# Sheet.net
KiCad netlist of a schematic drawn in Altium Designer
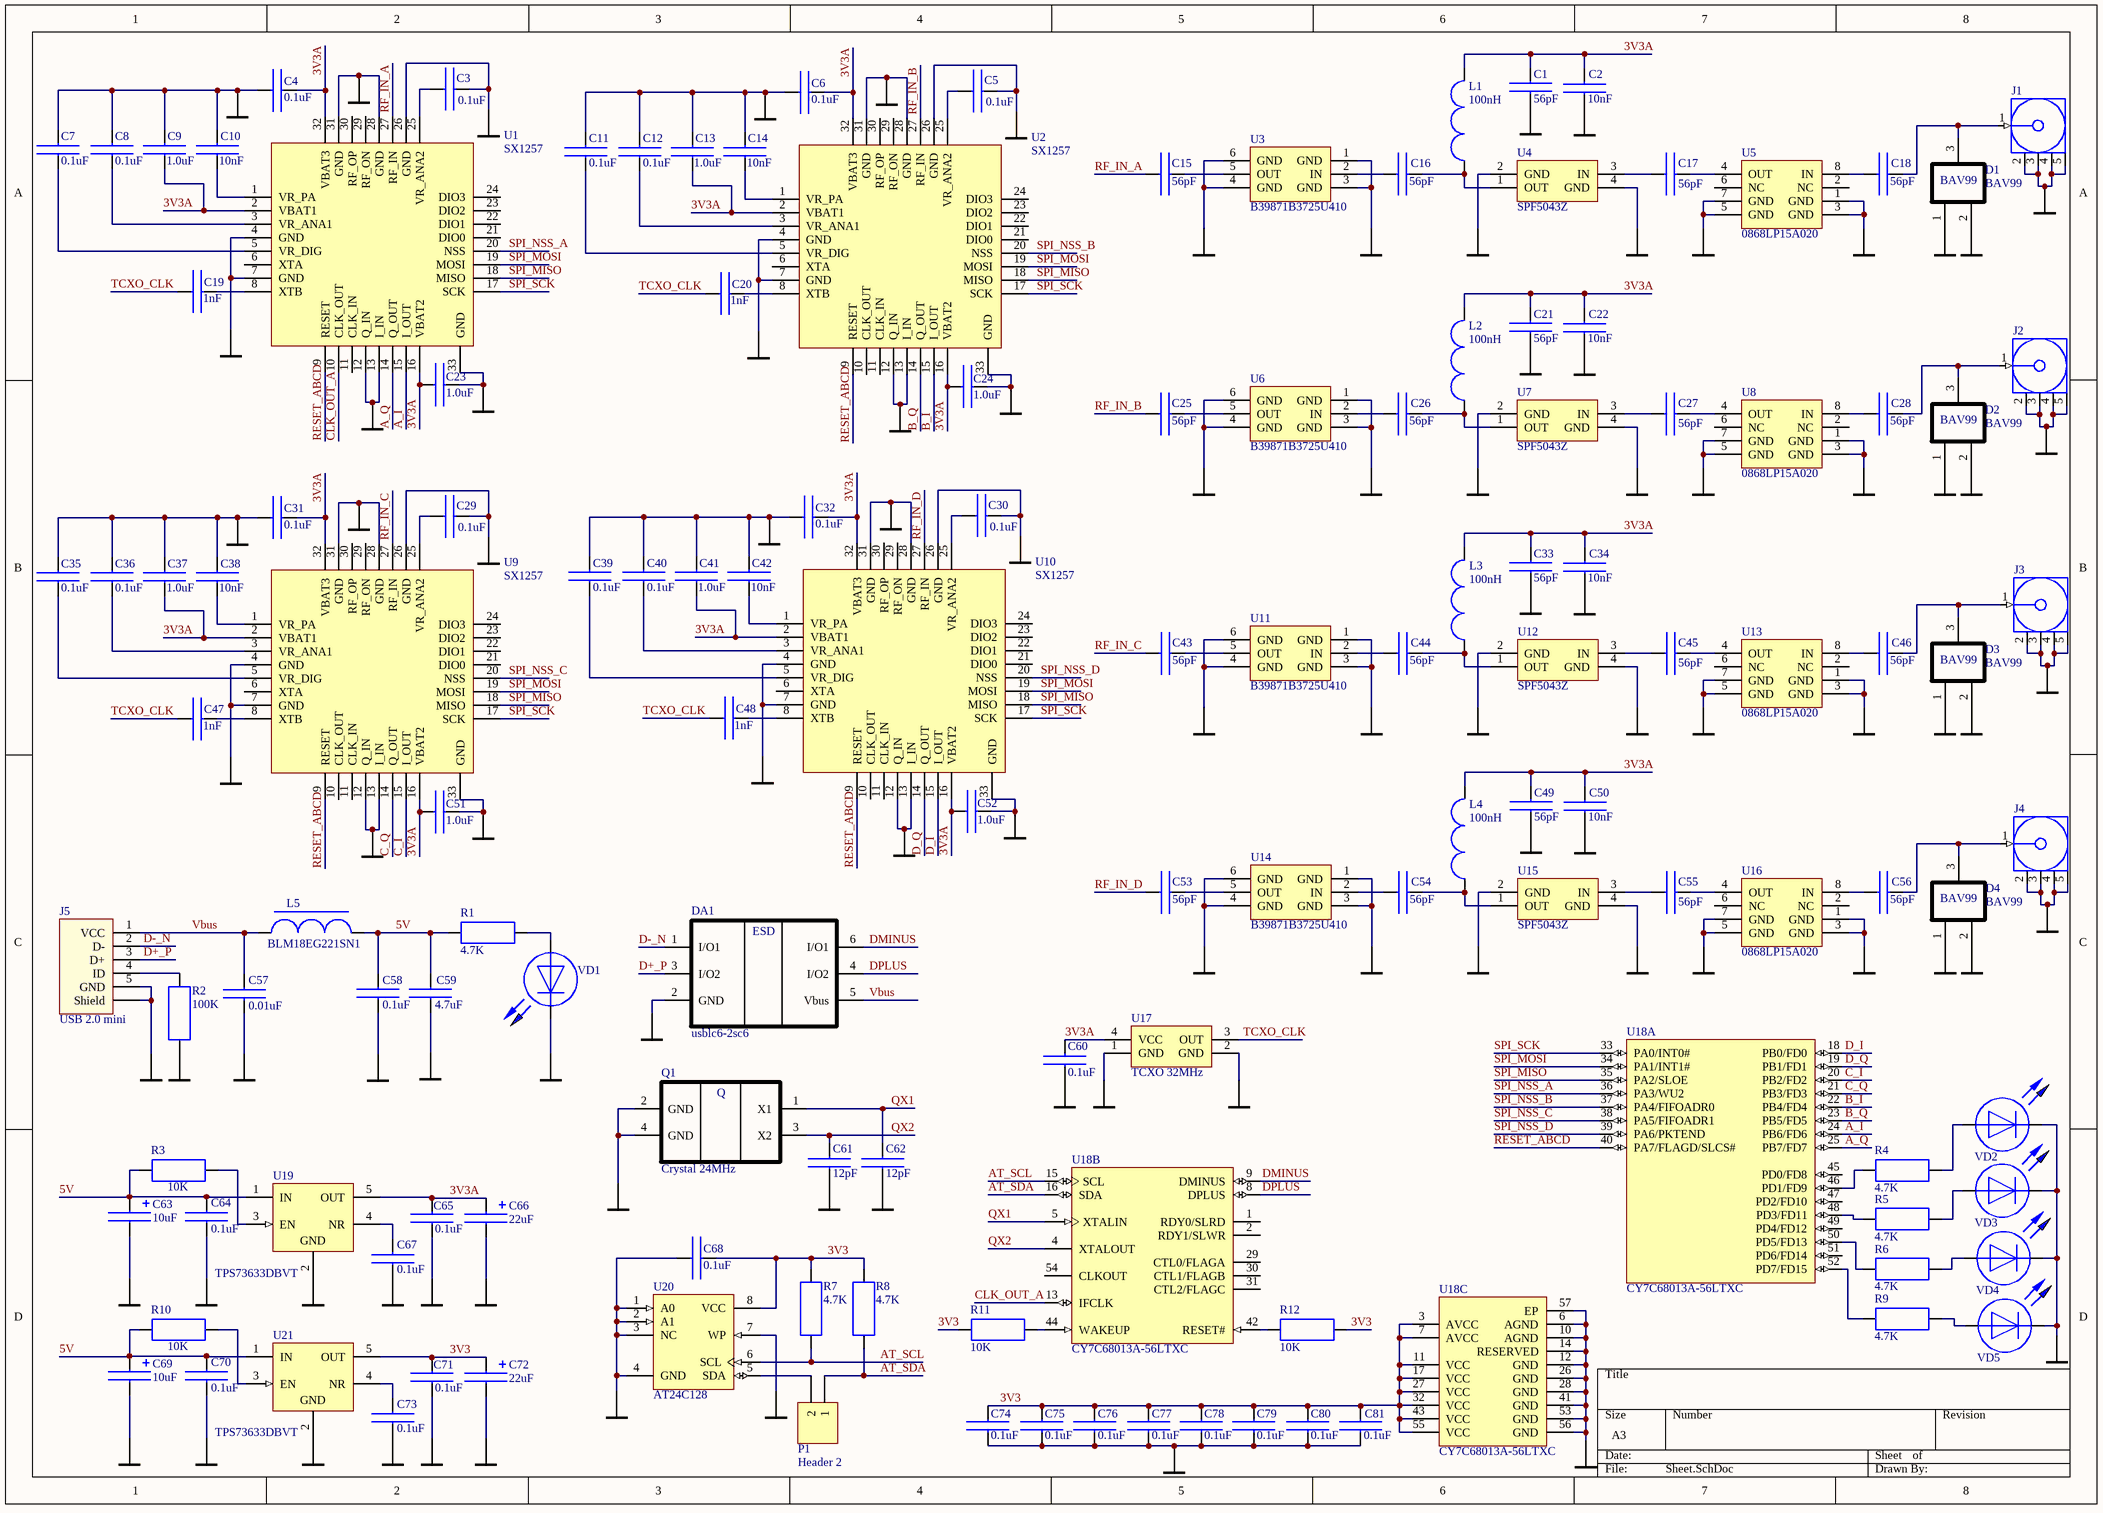
[diagram p0: Sheet.SchDoc]

(export (version "E")
  (design (tool "Eeschema 10.0.6"))
  (components
    (comp (ref "C1") (value "56pF") (footprint "CAP(0603)") (libsource (lib "Schlib1") (part "CAP")))
    (comp (ref "C2") (value "10nF") (footprint "CAP(0603)") (libsource (lib "Schlib1") (part "CAP")))
    (comp (ref "C3") (value "0.1uF") (footprint "CAP(0603)") (libsource (lib "Schlib1") (part "CAP")))
    (comp (ref "C4") (value "0.1uF") (footprint "CAP(0603)") (libsource (lib "Schlib1") (part "CAP")))
    (comp (ref "C5") (value "0.1uF") (footprint "CAP(0603)") (libsource (lib "Schlib1") (part "CAP")))
    (comp (ref "C6") (value "0.1uF") (footprint "CAP(0603)") (libsource (lib "Schlib1") (part "CAP")))
    (comp (ref "C7") (value "0.1uF") (footprint "CAP(0603)") (libsource (lib "Schlib1") (part "CAP")))
    (comp (ref "C8") (value "0.1uF") (footprint "CAP(0603)") (libsource (lib "Schlib1") (part "CAP")))
    (comp (ref "C9") (value "1.0uF") (footprint "CAP(0603)") (libsource (lib "Schlib1") (part "CAP")))
    (comp (ref "C10") (value "10nF") (footprint "CAP(0603)") (libsource (lib "Schlib1") (part "CAP")))
    (comp (ref "C11") (value "0.1uF") (footprint "CAP(0603)") (libsource (lib "Schlib1") (part "CAP")))
    (comp (ref "C12") (value "0.1uF") (footprint "CAP(0603)") (libsource (lib "Schlib1") (part "CAP")))
    (comp (ref "C13") (value "1.0uF") (footprint "CAP(0603)") (libsource (lib "Schlib1") (part "CAP")))
    (comp (ref "C14") (value "10nF") (footprint "CAP(0603)") (libsource (lib "Schlib1") (part "CAP")))
    (comp (ref "C15") (value "56pF") (footprint "CAP(0603)") (libsource (lib "Schlib1") (part "CAP")))
    (comp (ref "C16") (value "56pF") (footprint "CAP(0603)") (libsource (lib "Schlib1") (part "CAP")))
    (comp (ref "C17") (value "56pF") (footprint "CAP(0603)") (libsource (lib "Schlib1") (part "CAP")))
    (comp (ref "C18") (value "56pF") (footprint "CAP(0603)") (libsource (lib "Schlib1") (part "CAP")))
    (comp (ref "C19") (value "1nF") (footprint "CAP(0603)") (libsource (lib "Schlib1") (part "CAP")))
    (comp (ref "C20") (value "1nF") (footprint "CAP(0603)") (libsource (lib "Schlib1") (part "CAP")))
    (comp (ref "C21") (value "56pF") (footprint "CAP(0603)") (libsource (lib "Schlib1") (part "CAP")))
    (comp (ref "C22") (value "10nF") (footprint "CAP(0603)") (libsource (lib "Schlib1") (part "CAP")))
    (comp (ref "C23") (value "1.0uF") (footprint "CAP(0603)") (libsource (lib "Schlib1") (part "CAP")))
    (comp (ref "C24") (value "1.0uF") (footprint "CAP(0603)") (libsource (lib "Schlib1") (part "CAP")))
    (comp (ref "C25") (value "56pF") (footprint "CAP(0603)") (libsource (lib "Schlib1") (part "CAP")))
    (comp (ref "C26") (value "56pF") (footprint "CAP(0603)") (libsource (lib "Schlib1") (part "CAP")))
    (comp (ref "C27") (value "56pF") (footprint "CAP(0603)") (libsource (lib "Schlib1") (part "CAP")))
    (comp (ref "C28") (value "56pF") (footprint "CAP(0603)") (libsource (lib "Schlib1") (part "CAP")))
    (comp (ref "C29") (value "0.1uF") (footprint "CAP(0603)") (libsource (lib "Schlib1") (part "CAP")))
    (comp (ref "C30") (value "0.1uF") (footprint "CAP(0603)") (libsource (lib "Schlib1") (part "CAP")))
    (comp (ref "C31") (value "0.1uF") (footprint "CAP(0603)") (libsource (lib "Schlib1") (part "CAP")))
    (comp (ref "C32") (value "0.1uF") (footprint "CAP(0603)") (libsource (lib "Schlib1") (part "CAP")))
    (comp (ref "C33") (value "56pF") (footprint "CAP(0603)") (libsource (lib "Schlib1") (part "CAP")))
    (comp (ref "C34") (value "10nF") (footprint "CAP(0603)") (libsource (lib "Schlib1") (part "CAP")))
    (comp (ref "C35") (value "0.1uF") (footprint "CAP(0603)") (libsource (lib "Schlib1") (part "CAP")))
    (comp (ref "C36") (value "0.1uF") (footprint "CAP(0603)") (libsource (lib "Schlib1") (part "CAP")))
    (comp (ref "C37") (value "1.0uF") (footprint "CAP(0603)") (libsource (lib "Schlib1") (part "CAP")))
    (comp (ref "C38") (value "10nF") (footprint "CAP(0603)") (libsource (lib "Schlib1") (part "CAP")))
    (comp (ref "C39") (value "0.1uF") (footprint "CAP(0603)") (libsource (lib "Schlib1") (part "CAP")))
    (comp (ref "C40") (value "0.1uF") (footprint "CAP(0603)") (libsource (lib "Schlib1") (part "CAP")))
    (comp (ref "C41") (value "1.0uF") (footprint "CAP(0603)") (libsource (lib "Schlib1") (part "CAP")))
    (comp (ref "C42") (value "10nF") (footprint "CAP(0603)") (libsource (lib "Schlib1") (part "CAP")))
    (comp (ref "C43") (value "56pF") (footprint "CAP(0603)") (libsource (lib "Schlib1") (part "CAP")))
    (comp (ref "C44") (value "56pF") (footprint "CAP(0603)") (libsource (lib "Schlib1") (part "CAP")))
    (comp (ref "C45") (value "56pF") (footprint "CAP(0603)") (libsource (lib "Schlib1") (part "CAP")))
    (comp (ref "C46") (value "56pF") (footprint "CAP(0603)") (libsource (lib "Schlib1") (part "CAP")))
    (comp (ref "C47") (value "1nF") (footprint "CAP(0603)") (libsource (lib "Schlib1") (part "CAP")))
    (comp (ref "C48") (value "1nF") (footprint "CAP(0603)") (libsource (lib "Schlib1") (part "CAP")))
    (comp (ref "C49") (value "56pF") (footprint "CAP(0603)") (libsource (lib "Schlib1") (part "CAP")))
    (comp (ref "C50") (value "10nF") (footprint "CAP(0603)") (libsource (lib "Schlib1") (part "CAP")))
    (comp (ref "C51") (value "1.0uF") (footprint "CAP(0603)") (libsource (lib "Schlib1") (part "CAP")))
    (comp (ref "C52") (value "1.0uF") (footprint "CAP(0603)") (libsource (lib "Schlib1") (part "CAP")))
    (comp (ref "C53") (value "56pF") (footprint "CAP(0603)") (libsource (lib "Schlib1") (part "CAP")))
    (comp (ref "C54") (value "56pF") (footprint "CAP(0603)") (libsource (lib "Schlib1") (part "CAP")))
    (comp (ref "C55") (value "56pF") (footprint "CAP(0603)") (libsource (lib "Schlib1") (part "CAP")))
    (comp (ref "C56") (value "56pF") (footprint "CAP(0603)") (libsource (lib "Schlib1") (part "CAP")))
    (comp (ref "C57") (value "0.01uF") (footprint "CAP(0603)") (libsource (lib "Schlib1") (part "CAP")))
    (comp (ref "C58") (value "0.1uF") (footprint "CAP(0603)") (libsource (lib "Schlib1") (part "CAP")))
    (comp (ref "C59") (value "4.7uF") (footprint "CAP(0603)") (libsource (lib "Schlib1") (part "CAP")))
    (comp (ref "C60") (value "0.1uF") (footprint "CAP(0603)") (libsource (lib "Schlib1") (part "CAP")))
    (comp (ref "C61") (value "12pF") (footprint "CAP(0603)") (libsource (lib "Schlib1") (part "CAP")))
    (comp (ref "C62") (value "12pF") (footprint "CAP(0603)") (libsource (lib "Schlib1") (part "CAP")))
    (comp (ref "C63")
      (value "10uF")
      (footprint "CC3216(1206)x18")
      (description "Tantalum SMD capacitor")
      (libsource (lib "Schlib1") (part "Tantalum"))
    )
    (comp (ref "C64") (value "0.1uF") (footprint "CAP(0603)") (libsource (lib "Schlib1") (part "CAP")))
    (comp (ref "C65") (value "0.1uF") (footprint "CAP(0603)") (libsource (lib "Schlib1") (part "CAP")))
    (comp (ref "C66")
      (value "22uF")
      (footprint "CC3216(1206)x18")
      (description "Tantalum SMD capacitor")
      (libsource (lib "Schlib1") (part "Tantalum"))
    )
    (comp (ref "C67") (value "0.1uF") (footprint "CAP(0603)") (libsource (lib "Schlib1") (part "CAP")))
    (comp (ref "C68") (value "0.1uF") (footprint "CAP(0603)") (libsource (lib "Schlib1") (part "CAP")))
    (comp (ref "C69")
      (value "10uF")
      (footprint "CC3216(1206)x18")
      (description "Tantalum SMD capacitor")
      (libsource (lib "Schlib1") (part "Tantalum"))
    )
    (comp (ref "C70") (value "0.1uF") (footprint "CAP(0603)") (libsource (lib "Schlib1") (part "CAP")))
    (comp (ref "C71") (value "0.1uF") (footprint "CAP(0603)") (libsource (lib "Schlib1") (part "CAP")))
    (comp (ref "C72")
      (value "22uF")
      (footprint "CC3216(1206)x18")
      (description "Tantalum SMD capacitor")
      (libsource (lib "Schlib1") (part "Tantalum"))
    )
    (comp (ref "C73") (value "0.1uF") (footprint "CAP(0603)") (libsource (lib "Schlib1") (part "CAP")))
    (comp (ref "C74") (value "0.1uF") (footprint "CAP(0603)") (libsource (lib "Schlib1") (part "CAP")))
    (comp (ref "C75") (value "0.1uF") (footprint "CAP(0603)") (libsource (lib "Schlib1") (part "CAP")))
    (comp (ref "C76") (value "0.1uF") (footprint "CAP(0603)") (libsource (lib "Schlib1") (part "CAP")))
    (comp (ref "C77") (value "0.1uF") (footprint "CAP(0603)") (libsource (lib "Schlib1") (part "CAP")))
    (comp (ref "C78") (value "0.1uF") (footprint "CAP(0603)") (libsource (lib "Schlib1") (part "CAP")))
    (comp (ref "C79") (value "0.1uF") (footprint "CAP(0603)") (libsource (lib "Schlib1") (part "CAP")))
    (comp (ref "C80") (value "0.1uF") (footprint "CAP(0603)") (libsource (lib "Schlib1") (part "CAP")))
    (comp (ref "C81") (value "0.1uF") (footprint "CAP(0603)") (libsource (lib "Schlib1") (part "CAP")))
    (comp (ref "D1") (value "BAV99") (footprint "SOT-23B") (libsource (lib "Schlib1") (part "BAV99")))
    (comp (ref "D2") (value "BAV99") (footprint "SOT-23B") (libsource (lib "Schlib1") (part "BAV99")))
    (comp (ref "D3") (value "BAV99") (footprint "SOT-23B") (libsource (lib "Schlib1") (part "BAV99")))
    (comp (ref "D4") (value "BAV99") (footprint "SOT-23B") (libsource (lib "Schlib1") (part "BAV99")))
    (comp (ref "DA1")
      (value "usblc6-2sc6")
      (footprint "SOT23-6L")
      (libsource (lib "Schlib1") (part "usblc6-2sc6"))
    )
    (comp (ref "J1")
      (value "60312202114514")
      (footprint "60312202114514")
      (description "WR-SMA SMA PCB End Launch Jack Flat Tab for 1.6 mm PCB")
      (fields (field (name "PUBLISHER") "Wurth Elektronik"))
      (libsource (lib "Schlib1") (part "60312202114514"))
    )
    (comp (ref "J2")
      (value "60312202114514")
      (footprint "60312202114514")
      (description "WR-SMA SMA PCB End Launch Jack Flat Tab for 1.6 mm PCB")
      (fields (field (name "PUBLISHER") "Wurth Elektronik"))
      (libsource (lib "Schlib1") (part "60312202114514"))
    )
    (comp (ref "J3")
      (value "60312202114514")
      (footprint "60312202114514")
      (description "WR-SMA SMA PCB End Launch Jack Flat Tab for 1.6 mm PCB")
      (fields (field (name "PUBLISHER") "Wurth Elektronik"))
      (libsource (lib "Schlib1") (part "60312202114514"))
    )
    (comp (ref "J4")
      (value "60312202114514")
      (footprint "60312202114514")
      (description "WR-SMA SMA PCB End Launch Jack Flat Tab for 1.6 mm PCB")
      (fields (field (name "PUBLISHER") "Wurth Elektronik"))
      (libsource (lib "Schlib1") (part "60312202114514"))
    )
    (comp (ref "J5")
      (value "USB 2.0 mini")
      (footprint "65100516121")
      (description "Mini USB 2.0 Type B SMT Horizontal 5 Contacts WR-COM")
      (libsource (lib "Schlib1") (part "USB 2.0 mini"))
    )
    (comp (ref "L1") (value "100nH") (footprint "L_0603") (libsource (lib "Schlib1") (part "IND")))
    (comp (ref "L2") (value "100nH") (footprint "L_0603") (libsource (lib "Schlib1") (part "IND")))
    (comp (ref "L3") (value "100nH") (footprint "L_0603") (libsource (lib "Schlib1") (part "IND")))
    (comp (ref "L4") (value "100nH") (footprint "L_0603") (libsource (lib "Schlib1") (part "IND")))
    (comp (ref "L5")
      (value "BLM18EG221SN1")
      (footprint "BLM18EG221SN1")
      (description "SMD Ferrite Bead 2A 220 Ohm(100MHz)")
      (libsource (lib "Schlib1") (part "BLM18EG221SN1"))
    )
    (comp (ref "P1")
      (value "Header 2")
      (footprint "HDR1X2")
      (description "Header, 2-Pin")
      (fields (field (name "PUBLISHER") "Altium Limited"))
      (libsource (lib "Miscellaneous Connectors") (part "Header 2"))
    )
    (comp (ref "Q1")
      (value "Crystal 24MHz")
      (footprint "SMD3225")
      (libsource (lib "Schlib1") (part "Crystal 24MHz"))
    )
    (comp (ref "R1")
      (value "4.7K")
      (footprint "RES(0603)")
      (description "Chip Resistor")
      (libsource (lib "Schlib1") (part "RES"))
    )
    (comp (ref "R2")
      (value "100K")
      (footprint "RES(0603)")
      (description "Chip Resistor")
      (libsource (lib "Schlib1") (part "RES"))
    )
    (comp (ref "R3")
      (value "10K")
      (footprint "RES(0603)")
      (description "Chip Resistor")
      (libsource (lib "Schlib1") (part "RES"))
    )
    (comp (ref "R4")
      (value "4.7K")
      (footprint "RES(0603)")
      (description "Chip Resistor")
      (libsource (lib "Schlib1") (part "RES"))
    )
    (comp (ref "R5")
      (value "4.7K")
      (footprint "RES(0603)")
      (description "Chip Resistor")
      (libsource (lib "Schlib1") (part "RES"))
    )
    (comp (ref "R6")
      (value "4.7K")
      (footprint "RES(0603)")
      (description "Chip Resistor")
      (libsource (lib "Schlib1") (part "RES"))
    )
    (comp (ref "R7")
      (value "4.7K")
      (footprint "RES(0603)")
      (description "Chip Resistor")
      (libsource (lib "Schlib1") (part "RES"))
    )
    (comp (ref "R8")
      (value "4.7K")
      (footprint "RES(0603)")
      (description "Chip Resistor")
      (libsource (lib "Schlib1") (part "RES"))
    )
    (comp (ref "R9")
      (value "4.7K")
      (footprint "RES(0603)")
      (description "Chip Resistor")
      (libsource (lib "Schlib1") (part "RES"))
    )
    (comp (ref "R10")
      (value "10K")
      (footprint "RES(0603)")
      (description "Chip Resistor")
      (libsource (lib "Schlib1") (part "RES"))
    )
    (comp (ref "R11")
      (value "10K")
      (footprint "RES(0603)")
      (description "Chip Resistor")
      (libsource (lib "Schlib1") (part "RES"))
    )
    (comp (ref "R12")
      (value "10K")
      (footprint "RES(0603)")
      (description "Chip Resistor")
      (libsource (lib "Schlib1") (part "RES"))
    )
    (comp (ref "U1") (value "SX1257") (footprint "QFN-32") (libsource (lib "Schlib1") (part "SX1257")))
    (comp (ref "U2") (value "SX1257") (footprint "QFN-32") (libsource (lib "Schlib1") (part "SX1257")))
    (comp (ref "U3")
      (value "B39871B3725U410")
      (footprint "SAW_Filter")
      (description "SAW Filter, 869MHz Center")
      (libsource (lib "Schlib1") (part "B39871B3725U410"))
    )
    (comp (ref "U4") (value "SPF5043Z") (footprint "SOT343-4") (libsource (lib "Schlib1") (part "SPF5043Z")))
    (comp (ref "U5")
      (value "0868LP15A020")
      (footprint "LPF868")
      (libsource (lib "Schlib1") (part "0868LP15A020"))
    )
    (comp (ref "U6")
      (value "B39871B3725U410")
      (footprint "SAW_Filter")
      (description "SAW Filter, 869MHz Center")
      (libsource (lib "Schlib1") (part "B39871B3725U410"))
    )
    (comp (ref "U7") (value "SPF5043Z") (footprint "SOT343-4") (libsource (lib "Schlib1") (part "SPF5043Z")))
    (comp (ref "U8")
      (value "0868LP15A020")
      (footprint "LPF868")
      (libsource (lib "Schlib1") (part "0868LP15A020"))
    )
    (comp (ref "U9") (value "SX1257") (footprint "QFN-32") (libsource (lib "Schlib1") (part "SX1257")))
    (comp (ref "U10") (value "SX1257") (footprint "QFN-32") (libsource (lib "Schlib1") (part "SX1257")))
    (comp (ref "U11")
      (value "B39871B3725U410")
      (footprint "SAW_Filter")
      (description "SAW Filter, 869MHz Center")
      (libsource (lib "Schlib1") (part "B39871B3725U410"))
    )
    (comp (ref "U12") (value "SPF5043Z") (footprint "SOT343-4") (libsource (lib "Schlib1") (part "SPF5043Z")))
    (comp (ref "U13")
      (value "0868LP15A020")
      (footprint "LPF868")
      (libsource (lib "Schlib1") (part "0868LP15A020"))
    )
    (comp (ref "U14")
      (value "B39871B3725U410")
      (footprint "SAW_Filter")
      (description "SAW Filter, 869MHz Center")
      (libsource (lib "Schlib1") (part "B39871B3725U410"))
    )
    (comp (ref "U15") (value "SPF5043Z") (footprint "SOT343-4") (libsource (lib "Schlib1") (part "SPF5043Z")))
    (comp (ref "U16")
      (value "0868LP15A020")
      (footprint "LPF868")
      (libsource (lib "Schlib1") (part "0868LP15A020"))
    )
    (comp (ref "U17") (value "TCXO 32MHz") (footprint "TCXO") (libsource (lib "Schlib1") (part "TCXO")))
    (comp (ref "U18")
      (value "CY7C68013A-56LTXC")
      (footprint "CYP-LTX56-5200X4500TP_N")
      (libsource (lib "Schlib1") (part "CY7C68013A-56LTXC"))
    )
    (comp (ref "U19")
      (value "TPS73633DBVT")
      (footprint "TI-DBV5_N")
      (fields (field (name "MANUFACTURER") "Texas Instruments"))
      (libsource (lib "Schlib1") (part "TPS73633DBVT"))
    )
    (comp (ref "U20") (value "AT24C128") (footprint "8S1_N") (libsource (lib "Schlib1") (part "AT24C128")))
    (comp (ref "U21")
      (value "TPS73633DBVT")
      (footprint "TI-DBV5_N")
      (fields (field (name "MANUFACTURER") "Texas Instruments"))
      (libsource (lib "Schlib1") (part "TPS73633DBVT"))
    )
    (comp (ref "VD1") (value "VD_6") (footprint "LED_0603") (libsource (lib "Schlib1") (part "VD_6")))
    (comp (ref "VD2") (value "VD_6") (footprint "LED_0603") (libsource (lib "Schlib1") (part "VD_6")))
    (comp (ref "VD3") (value "VD_6") (footprint "LED_0603") (libsource (lib "Schlib1") (part "VD_6")))
    (comp (ref "VD4") (value "VD_6") (footprint "LED_0603") (libsource (lib "Schlib1") (part "VD_6")))
    (comp (ref "VD5") (value "VD_6") (footprint "LED_0603") (libsource (lib "Schlib1") (part "VD_6")))
  )
  (nets
    (net (code "1") (name "/3V3") (class "Default")
      (node (ref "C68") (pin "2") (pintype "passive"))
      (node (ref "C71") (pin "2") (pintype "passive"))
      (node (ref "C72") (pin "1") (pintype "passive"))
      (node (ref "C74") (pin "2") (pintype "passive"))
      (node (ref "C75") (pin "2") (pintype "passive"))
      (node (ref "C76") (pin "2") (pintype "passive"))
      (node (ref "C77") (pin "2") (pintype "passive"))
      (node (ref "C78") (pin "2") (pintype "passive"))
      (node (ref "C79") (pin "2") (pintype "passive"))
      (node (ref "C80") (pin "2") (pintype "passive"))
      (node (ref "C81") (pin "2") (pintype "passive"))
      (node (ref "R11") (pin "1") (pintype "passive"))
      (node (ref "R12") (pin "2") (pintype "passive"))
      (node (ref "R7") (pin "2") (pintype "passive"))
      (node (ref "R8") (pin "2") (pintype "passive"))
      (node (ref "U18") (pin "11") (pinfunction "VCC_11") (pintype "power_in"))
      (node (ref "U18") (pin "17") (pinfunction "VCC_17") (pintype "power_in"))
      (node (ref "U18") (pin "27") (pinfunction "VCC_27") (pintype "power_in"))
      (node (ref "U18") (pin "3") (pinfunction "AVCC_3") (pintype "power_in"))
      (node (ref "U18") (pin "32") (pinfunction "VCC_32") (pintype "power_in"))
      (node (ref "U18") (pin "43") (pinfunction "VCC_43") (pintype "power_in"))
      (node (ref "U18") (pin "55") (pinfunction "VCC_55") (pintype "power_in"))
      (node (ref "U18") (pin "7") (pinfunction "AVCC_7") (pintype "power_in"))
      (node (ref "U20") (pin "8") (pinfunction "VCC_8") (pintype "power_in"))
      (node (ref "U21") (pin "5") (pinfunction "OUT_5") (pintype "power_in"))
    )
    (net (code "2") (name "/3V3A") (class "Default")
      (node (ref "C1") (pin "2") (pintype "passive"))
      (node (ref "C13") (pin "1") (pintype "passive"))
      (node (ref "C2") (pin "2") (pintype "passive"))
      (node (ref "C21") (pin "2") (pintype "passive"))
      (node (ref "C22") (pin "2") (pintype "passive"))
      (node (ref "C23") (pin "2") (pintype "passive"))
      (node (ref "C24") (pin "2") (pintype "passive"))
      (node (ref "C31") (pin "2") (pintype "passive"))
      (node (ref "C32") (pin "2") (pintype "passive"))
      (node (ref "C33") (pin "2") (pintype "passive"))
      (node (ref "C34") (pin "2") (pintype "passive"))
      (node (ref "C37") (pin "1") (pintype "passive"))
      (node (ref "C4") (pin "2") (pintype "passive"))
      (node (ref "C41") (pin "1") (pintype "passive"))
      (node (ref "C49") (pin "2") (pintype "passive"))
      (node (ref "C50") (pin "2") (pintype "passive"))
      (node (ref "C51") (pin "2") (pintype "passive"))
      (node (ref "C52") (pin "2") (pintype "passive"))
      (node (ref "C6") (pin "2") (pintype "passive"))
      (node (ref "C60") (pin "2") (pintype "passive"))
      (node (ref "C65") (pin "2") (pintype "passive"))
      (node (ref "C66") (pin "1") (pintype "passive"))
      (node (ref "C9") (pin "1") (pintype "passive"))
      (node (ref "L1") (pin "2") (pintype "passive"))
      (node (ref "L2") (pin "2") (pintype "passive"))
      (node (ref "L3") (pin "2") (pintype "passive"))
      (node (ref "L4") (pin "2") (pintype "passive"))
      (node (ref "U1") (pin "16") (pinfunction "VBAT2_16") (pintype "passive"))
      (node (ref "U1") (pin "2") (pinfunction "VBAT1_2") (pintype "passive"))
      (node (ref "U1") (pin "32") (pinfunction "VBAT3_32") (pintype "passive"))
      (node (ref "U10") (pin "16") (pinfunction "VBAT2_16") (pintype "passive"))
      (node (ref "U10") (pin "2") (pinfunction "VBAT1_2") (pintype "passive"))
      (node (ref "U10") (pin "32") (pinfunction "VBAT3_32") (pintype "passive"))
      (node (ref "U17") (pin "4") (pinfunction "VCC_4") (pintype "passive"))
      (node (ref "U19") (pin "5") (pinfunction "OUT_5") (pintype "power_in"))
      (node (ref "U2") (pin "16") (pinfunction "VBAT2_16") (pintype "passive"))
      (node (ref "U2") (pin "2") (pinfunction "VBAT1_2") (pintype "passive"))
      (node (ref "U2") (pin "32") (pinfunction "VBAT3_32") (pintype "passive"))
      (node (ref "U9") (pin "16") (pinfunction "VBAT2_16") (pintype "passive"))
      (node (ref "U9") (pin "2") (pinfunction "VBAT1_2") (pintype "passive"))
      (node (ref "U9") (pin "32") (pinfunction "VBAT3_32") (pintype "passive"))
    )
    (net (code "3") (name "/5V") (class "Default")
      (node (ref "C58") (pin "2") (pintype "passive"))
      (node (ref "C59") (pin "2") (pintype "passive"))
      (node (ref "C63") (pin "1") (pintype "passive"))
      (node (ref "C64") (pin "2") (pintype "passive"))
      (node (ref "C69") (pin "1") (pintype "passive"))
      (node (ref "C70") (pin "2") (pintype "passive"))
      (node (ref "L5") (pin "2") (pintype "passive"))
      (node (ref "R1") (pin "1") (pintype "passive"))
      (node (ref "R10") (pin "1") (pintype "passive"))
      (node (ref "R3") (pin "1") (pintype "passive"))
      (node (ref "U19") (pin "1") (pinfunction "IN_1") (pintype "power_in"))
      (node (ref "U21") (pin "1") (pinfunction "IN_1") (pintype "power_in"))
    )
    (net (code "4") (name "/AT_SCL") (class "Default")
      (node (ref "R7") (pin "1") (pintype "passive"))
      (node (ref "U18") (pin "15") (pinfunction "SCL_15") (pintype "bidirectional"))
      (node (ref "U20") (pin "6") (pinfunction "SCL_6") (pintype "input"))
    )
    (net (code "5") (name "/AT_SDA") (class "Default")
      (node (ref "P1") (pin "1") (pinfunction "1_1") (pintype "passive"))
      (node (ref "R8") (pin "1") (pintype "passive"))
      (node (ref "U18") (pin "16") (pinfunction "SDA_16") (pintype "bidirectional"))
    )
    (net (code "6") (name "/A_I") (class "Default")
      (node (ref "U1") (pin "15") (pinfunction "I_OUT_15") (pintype "passive"))
      (node (ref "U18") (pin "24") (pinfunction "PB6/FD6_24") (pintype "bidirectional"))
    )
    (net (code "7") (name "/A_Q") (class "Default")
      (node (ref "U1") (pin "14") (pinfunction "Q_OUT_14") (pintype "passive"))
      (node (ref "U18") (pin "25") (pinfunction "PB7/FD7_25") (pintype "bidirectional"))
    )
    (net (code "8") (name "/B_I") (class "Default")
      (node (ref "U18") (pin "22") (pinfunction "PB4/FD4_22") (pintype "bidirectional"))
      (node (ref "U2") (pin "15") (pinfunction "I_OUT_15") (pintype "passive"))
    )
    (net (code "9") (name "/B_Q") (class "Default")
      (node (ref "U18") (pin "23") (pinfunction "PB5/FD5_23") (pintype "bidirectional"))
      (node (ref "U2") (pin "14") (pinfunction "Q_OUT_14") (pintype "passive"))
    )
    (net (code "10") (name "/CLK_OUT_A") (class "Default")
      (node (ref "U1") (pin "10") (pinfunction "CLK_OUT_10") (pintype "passive"))
      (node (ref "U18") (pin "13") (pinfunction "IFCLK_13") (pintype "bidirectional"))
    )
    (net (code "11") (name "/C_I") (class "Default")
      (node (ref "U18") (pin "20") (pinfunction "PB2/FD2_20") (pintype "bidirectional"))
      (node (ref "U9") (pin "15") (pinfunction "I_OUT_15") (pintype "passive"))
    )
    (net (code "12") (name "/C_Q") (class "Default")
      (node (ref "U18") (pin "21") (pinfunction "PB3/FD3_21") (pintype "bidirectional"))
      (node (ref "U9") (pin "14") (pinfunction "Q_OUT_14") (pintype "passive"))
    )
    (net (code "13") (name "/D+_P") (class "Default")
      (node (ref "DA1") (pin "3") (pinfunction "I/O2_3") (pintype "passive"))
      (node (ref "J5") (pin "3") (pinfunction "D+_3") (pintype "passive"))
    )
    (net (code "14") (name "/D-_N") (class "Default")
      (node (ref "DA1") (pin "1") (pinfunction "I/O1_1") (pintype "passive"))
      (node (ref "J5") (pin "2") (pinfunction "D-_2") (pintype "passive"))
    )
    (net (code "15") (name "/DMINUS") (class "Default")
      (node (ref "DA1") (pin "6") (pinfunction "I/O1_6") (pintype "passive"))
      (node (ref "U18") (pin "9") (pinfunction "DMINUS_9") (pintype "bidirectional"))
    )
    (net (code "16") (name "/DPLUS") (class "Default")
      (node (ref "DA1") (pin "4") (pinfunction "I/O2_4") (pintype "passive"))
      (node (ref "U18") (pin "8") (pinfunction "DPLUS_8") (pintype "bidirectional"))
    )
    (net (code "17") (name "/D_I") (class "Default")
      (node (ref "U10") (pin "15") (pinfunction "I_OUT_15") (pintype "passive"))
      (node (ref "U18") (pin "18") (pinfunction "PB0/FD0_18") (pintype "bidirectional"))
    )
    (net (code "18") (name "/D_Q") (class "Default")
      (node (ref "U10") (pin "14") (pinfunction "Q_OUT_14") (pintype "passive"))
      (node (ref "U18") (pin "19") (pinfunction "PB1/FD1_19") (pintype "bidirectional"))
    )
    (net (code "19") (name "/QX1") (class "Default")
      (node (ref "C62") (pin "2") (pintype "passive"))
      (node (ref "Q1") (pin "1") (pinfunction "X1_1") (pintype "passive"))
      (node (ref "U18") (pin "5") (pinfunction "XTALIN_5") (pintype "input"))
    )
    (net (code "20") (name "/QX2") (class "Default")
      (node (ref "C61") (pin "2") (pintype "passive"))
      (node (ref "Q1") (pin "3") (pinfunction "X2_3") (pintype "passive"))
      (node (ref "U18") (pin "4") (pinfunction "XTALOUT_4") (pintype "passive"))
    )
    (net (code "21") (name "/RESET_ABCD") (class "Default")
      (node (ref "U1") (pin "9") (pinfunction "RESET_9") (pintype "passive"))
      (node (ref "U10") (pin "9") (pinfunction "RESET_9") (pintype "passive"))
      (node (ref "U18") (pin "40") (pinfunction "PA7/FLAGD/SLCS#_40") (pintype "bidirectional"))
      (node (ref "U2") (pin "9") (pinfunction "RESET_9") (pintype "passive"))
      (node (ref "U9") (pin "9") (pinfunction "RESET_9") (pintype "passive"))
    )
    (net (code "22") (name "/RF_IN_A") (class "Default")
      (node (ref "C15") (pin "1") (pintype "passive"))
      (node (ref "U1") (pin "27") (pinfunction "RF_IN_27") (pintype "passive"))
    )
    (net (code "23") (name "/RF_IN_B") (class "Default")
      (node (ref "C25") (pin "1") (pintype "passive"))
      (node (ref "U2") (pin "27") (pinfunction "RF_IN_27") (pintype "passive"))
    )
    (net (code "24") (name "/RF_IN_C") (class "Default")
      (node (ref "C43") (pin "1") (pintype "passive"))
      (node (ref "U9") (pin "27") (pinfunction "RF_IN_27") (pintype "passive"))
    )
    (net (code "25") (name "/RF_IN_D") (class "Default")
      (node (ref "C53") (pin "1") (pintype "passive"))
      (node (ref "U10") (pin "27") (pinfunction "RF_IN_27") (pintype "passive"))
    )
    (net (code "26") (name "/SPI_MISO") (class "Default")
      (node (ref "U1") (pin "18") (pinfunction "MISO_18") (pintype "passive"))
      (node (ref "U10") (pin "18") (pinfunction "MISO_18") (pintype "passive"))
      (node (ref "U18") (pin "35") (pinfunction "PA2/SLOE_35") (pintype "bidirectional"))
      (node (ref "U2") (pin "18") (pinfunction "MISO_18") (pintype "passive"))
      (node (ref "U9") (pin "18") (pinfunction "MISO_18") (pintype "passive"))
    )
    (net (code "27") (name "/SPI_MOSI") (class "Default")
      (node (ref "U1") (pin "19") (pinfunction "MOSI_19") (pintype "passive"))
      (node (ref "U10") (pin "19") (pinfunction "MOSI_19") (pintype "passive"))
      (node (ref "U18") (pin "34") (pinfunction "PA1/INT1#_34") (pintype "bidirectional"))
      (node (ref "U2") (pin "19") (pinfunction "MOSI_19") (pintype "passive"))
      (node (ref "U9") (pin "19") (pinfunction "MOSI_19") (pintype "passive"))
    )
    (net (code "28") (name "/SPI_NSS_A") (class "Default")
      (node (ref "U1") (pin "20") (pinfunction "NSS_20") (pintype "passive"))
      (node (ref "U18") (pin "36") (pinfunction "PA3/WU2_36") (pintype "bidirectional"))
    )
    (net (code "29") (name "/SPI_NSS_B") (class "Default")
      (node (ref "U18") (pin "37") (pinfunction "PA4/FIFOADR0_37") (pintype "bidirectional"))
      (node (ref "U2") (pin "20") (pinfunction "NSS_20") (pintype "passive"))
    )
    (net (code "30") (name "/SPI_NSS_C") (class "Default")
      (node (ref "U18") (pin "38") (pinfunction "PA5/FIFOADR1_38") (pintype "bidirectional"))
      (node (ref "U9") (pin "20") (pinfunction "NSS_20") (pintype "passive"))
    )
    (net (code "31") (name "/SPI_NSS_D") (class "Default")
      (node (ref "U10") (pin "20") (pinfunction "NSS_20") (pintype "passive"))
      (node (ref "U18") (pin "39") (pinfunction "PA6/PKTEND_39") (pintype "bidirectional"))
    )
    (net (code "32") (name "/SPI_SCK") (class "Default")
      (node (ref "U1") (pin "17") (pinfunction "SCK_17") (pintype "passive"))
      (node (ref "U10") (pin "17") (pinfunction "SCK_17") (pintype "passive"))
      (node (ref "U18") (pin "33") (pinfunction "PA0/INT0#_33") (pintype "bidirectional"))
      (node (ref "U2") (pin "17") (pinfunction "SCK_17") (pintype "passive"))
      (node (ref "U9") (pin "17") (pinfunction "SCK_17") (pintype "passive"))
    )
    (net (code "33") (name "/TCXO_CLK") (class "Default")
      (node (ref "C19") (pin "1") (pintype "passive"))
      (node (ref "C20") (pin "1") (pintype "passive"))
      (node (ref "C47") (pin "1") (pintype "passive"))
      (node (ref "C48") (pin "1") (pintype "passive"))
      (node (ref "U17") (pin "3") (pinfunction "OUT_3") (pintype "power_in"))
    )
    (net (code "34") (name "/Vbus") (class "Default")
      (node (ref "C57") (pin "2") (pintype "passive"))
      (node (ref "DA1") (pin "5") (pinfunction "Vbus_5") (pintype "passive"))
      (node (ref "J5") (pin "1") (pinfunction "VCC_1") (pintype "passive"))
      (node (ref "L5") (pin "1") (pintype "passive"))
    )
    (net (code "35") (name "GND") (class "Default")
      (node (ref "C1") (pin "1") (pintype "passive"))
      (node (ref "C10") (pin "2") (pintype "passive"))
      (node (ref "C11") (pin "2") (pintype "passive"))
      (node (ref "C12") (pin "2") (pintype "passive"))
      (node (ref "C13") (pin "2") (pintype "passive"))
      (node (ref "C14") (pin "2") (pintype "passive"))
      (node (ref "C2") (pin "1") (pintype "passive"))
      (node (ref "C21") (pin "1") (pintype "passive"))
      (node (ref "C22") (pin "1") (pintype "passive"))
      (node (ref "C23") (pin "1") (pintype "passive"))
      (node (ref "C24") (pin "1") (pintype "passive"))
      (node (ref "C29") (pin "2") (pintype "passive"))
      (node (ref "C3") (pin "2") (pintype "passive"))
      (node (ref "C30") (pin "2") (pintype "passive"))
      (node (ref "C31") (pin "1") (pintype "passive"))
      (node (ref "C32") (pin "1") (pintype "passive"))
      (node (ref "C33") (pin "1") (pintype "passive"))
      (node (ref "C34") (pin "1") (pintype "passive"))
      (node (ref "C35") (pin "2") (pintype "passive"))
      (node (ref "C36") (pin "2") (pintype "passive"))
      (node (ref "C37") (pin "2") (pintype "passive"))
      (node (ref "C38") (pin "2") (pintype "passive"))
      (node (ref "C39") (pin "2") (pintype "passive"))
      (node (ref "C4") (pin "1") (pintype "passive"))
      (node (ref "C40") (pin "2") (pintype "passive"))
      (node (ref "C41") (pin "2") (pintype "passive"))
      (node (ref "C42") (pin "2") (pintype "passive"))
      (node (ref "C49") (pin "1") (pintype "passive"))
      (node (ref "C5") (pin "2") (pintype "passive"))
      (node (ref "C50") (pin "1") (pintype "passive"))
      (node (ref "C51") (pin "1") (pintype "passive"))
      (node (ref "C52") (pin "1") (pintype "passive"))
      (node (ref "C57") (pin "1") (pintype "passive"))
      (node (ref "C58") (pin "1") (pintype "passive"))
      (node (ref "C59") (pin "1") (pintype "passive"))
      (node (ref "C6") (pin "1") (pintype "passive"))
      (node (ref "C60") (pin "1") (pintype "passive"))
      (node (ref "C61") (pin "1") (pintype "passive"))
      (node (ref "C62") (pin "1") (pintype "passive"))
      (node (ref "C63") (pin "2") (pintype "passive"))
      (node (ref "C64") (pin "1") (pintype "passive"))
      (node (ref "C65") (pin "1") (pintype "passive"))
      (node (ref "C66") (pin "2") (pintype "passive"))
      (node (ref "C67") (pin "1") (pintype "passive"))
      (node (ref "C68") (pin "1") (pintype "passive"))
      (node (ref "C69") (pin "2") (pintype "passive"))
      (node (ref "C7") (pin "2") (pintype "passive"))
      (node (ref "C70") (pin "1") (pintype "passive"))
      (node (ref "C71") (pin "1") (pintype "passive"))
      (node (ref "C72") (pin "2") (pintype "passive"))
      (node (ref "C73") (pin "1") (pintype "passive"))
      (node (ref "C74") (pin "1") (pintype "passive"))
      (node (ref "C75") (pin "1") (pintype "passive"))
      (node (ref "C76") (pin "1") (pintype "passive"))
      (node (ref "C77") (pin "1") (pintype "passive"))
      (node (ref "C78") (pin "1") (pintype "passive"))
      (node (ref "C79") (pin "1") (pintype "passive"))
      (node (ref "C8") (pin "2") (pintype "passive"))
      (node (ref "C80") (pin "1") (pintype "passive"))
      (node (ref "C81") (pin "1") (pintype "passive"))
      (node (ref "C9") (pin "2") (pintype "passive"))
      (node (ref "D1") (pin "1") (pintype "passive"))
      (node (ref "D1") (pin "2") (pintype "passive"))
      (node (ref "D2") (pin "1") (pintype "passive"))
      (node (ref "D2") (pin "2") (pintype "passive"))
      (node (ref "D3") (pin "1") (pintype "passive"))
      (node (ref "D3") (pin "2") (pintype "passive"))
      (node (ref "D4") (pin "1") (pintype "passive"))
      (node (ref "D4") (pin "2") (pintype "passive"))
      (node (ref "DA1") (pin "2") (pinfunction "GND_2") (pintype "passive"))
      (node (ref "J1") (pin "2") (pinfunction "GND_2") (pintype "power_in"))
      (node (ref "J1") (pin "3") (pinfunction "GND_3") (pintype "power_in"))
      (node (ref "J1") (pin "4") (pinfunction "GND_4") (pintype "power_in"))
      (node (ref "J1") (pin "5") (pinfunction "GND_5") (pintype "power_in"))
      (node (ref "J2") (pin "2") (pinfunction "GND_2") (pintype "power_in"))
      (node (ref "J2") (pin "3") (pinfunction "GND_3") (pintype "power_in"))
      (node (ref "J2") (pin "4") (pinfunction "GND_4") (pintype "power_in"))
      (node (ref "J2") (pin "5") (pinfunction "GND_5") (pintype "power_in"))
      (node (ref "J3") (pin "2") (pinfunction "GND_2") (pintype "power_in"))
      (node (ref "J3") (pin "3") (pinfunction "GND_3") (pintype "power_in"))
      (node (ref "J3") (pin "4") (pinfunction "GND_4") (pintype "power_in"))
      (node (ref "J3") (pin "5") (pinfunction "GND_5") (pintype "power_in"))
      (node (ref "J4") (pin "2") (pinfunction "GND_2") (pintype "power_in"))
      (node (ref "J4") (pin "3") (pinfunction "GND_3") (pintype "power_in"))
      (node (ref "J4") (pin "4") (pinfunction "GND_4") (pintype "power_in"))
      (node (ref "J4") (pin "5") (pinfunction "GND_5") (pintype "power_in"))
      (node (ref "J5") (pin "5") (pinfunction "GND_5") (pintype "passive"))
      (node (ref "J5") (pin "Shell") (pinfunction "Shield_Shell") (pintype "passive"))
      (node (ref "Q1") (pin "2") (pinfunction "GND_2") (pintype "passive"))
      (node (ref "Q1") (pin "4") (pinfunction "GND_4") (pintype "passive"))
      (node (ref "R2") (pin "1") (pintype "passive"))
      (node (ref "U1") (pin "12") (pinfunction "Q_IN_12") (pintype "passive"))
      (node (ref "U1") (pin "13") (pinfunction "I_IN_13") (pintype "passive"))
      (node (ref "U1") (pin "26") (pinfunction "GND_26") (pintype "passive"))
      (node (ref "U1") (pin "28") (pinfunction "GND_28") (pintype "passive"))
      (node (ref "U1") (pin "31") (pinfunction "GND_31") (pintype "passive"))
      (node (ref "U1") (pin "33") (pinfunction "GND_33") (pintype "passive"))
      (node (ref "U1") (pin "4") (pinfunction "GND_4") (pintype "passive"))
      (node (ref "U1") (pin "7") (pinfunction "GND_7") (pintype "passive"))
      (node (ref "U10") (pin "12") (pinfunction "Q_IN_12") (pintype "passive"))
      (node (ref "U10") (pin "13") (pinfunction "I_IN_13") (pintype "passive"))
      (node (ref "U10") (pin "26") (pinfunction "GND_26") (pintype "passive"))
      (node (ref "U10") (pin "28") (pinfunction "GND_28") (pintype "passive"))
      (node (ref "U10") (pin "31") (pinfunction "GND_31") (pintype "passive"))
      (node (ref "U10") (pin "33") (pinfunction "GND_33") (pintype "passive"))
      (node (ref "U10") (pin "4") (pinfunction "GND_4") (pintype "passive"))
      (node (ref "U10") (pin "7") (pinfunction "GND_7") (pintype "passive"))
      (node (ref "U11") (pin "1") (pinfunction "GND_1") (pintype "passive"))
      (node (ref "U11") (pin "3") (pinfunction "GND_3") (pintype "passive"))
      (node (ref "U11") (pin "4") (pinfunction "GND_4") (pintype "power_in"))
      (node (ref "U11") (pin "6") (pinfunction "GND_6") (pintype "passive"))
      (node (ref "U12") (pin "2") (pinfunction "GND_2") (pintype "power_in"))
      (node (ref "U12") (pin "4") (pinfunction "GND_4") (pintype "passive"))
      (node (ref "U13") (pin "1") (pinfunction "GND_1") (pintype "passive"))
      (node (ref "U13") (pin "3") (pinfunction "GND_3") (pintype "passive"))
      (node (ref "U13") (pin "5") (pinfunction "GND_5") (pintype "passive"))
      (node (ref "U13") (pin "7") (pinfunction "GND_7") (pintype "passive"))
      (node (ref "U14") (pin "1") (pinfunction "GND_1") (pintype "passive"))
      (node (ref "U14") (pin "3") (pinfunction "GND_3") (pintype "passive"))
      (node (ref "U14") (pin "4") (pinfunction "GND_4") (pintype "power_in"))
      (node (ref "U14") (pin "6") (pinfunction "GND_6") (pintype "passive"))
      (node (ref "U15") (pin "2") (pinfunction "GND_2") (pintype "power_in"))
      (node (ref "U15") (pin "4") (pinfunction "GND_4") (pintype "passive"))
      (node (ref "U16") (pin "1") (pinfunction "GND_1") (pintype "passive"))
      (node (ref "U16") (pin "3") (pinfunction "GND_3") (pintype "passive"))
      (node (ref "U16") (pin "5") (pinfunction "GND_5") (pintype "passive"))
      (node (ref "U16") (pin "7") (pinfunction "GND_7") (pintype "passive"))
      (node (ref "U17") (pin "1") (pinfunction "GND_1") (pintype "passive"))
      (node (ref "U17") (pin "2") (pinfunction "GND_2") (pintype "passive"))
      (node (ref "U18") (pin "10") (pinfunction "AGND_10") (pintype "power_in"))
      (node (ref "U18") (pin "12") (pinfunction "GND_12") (pintype "power_in"))
      (node (ref "U18") (pin "14") (pinfunction "RESERVED_14") (pintype "power_in"))
      (node (ref "U18") (pin "26") (pinfunction "GND_26") (pintype "power_in"))
      (node (ref "U18") (pin "28") (pinfunction "GND_28") (pintype "power_in"))
      (node (ref "U18") (pin "41") (pinfunction "GND_41") (pintype "power_in"))
      (node (ref "U18") (pin "53") (pinfunction "GND_53") (pintype "power_in"))
      (node (ref "U18") (pin "56") (pinfunction "GND_56") (pintype "power_in"))
      (node (ref "U18") (pin "57") (pinfunction "EP_57") (pintype "passive"))
      (node (ref "U18") (pin "6") (pinfunction "AGND_6") (pintype "power_in"))
      (node (ref "U19") (pin "2") (pinfunction "GND_2") (pintype "power_in"))
      (node (ref "U2") (pin "12") (pinfunction "Q_IN_12") (pintype "passive"))
      (node (ref "U2") (pin "13") (pinfunction "I_IN_13") (pintype "passive"))
      (node (ref "U2") (pin "26") (pinfunction "GND_26") (pintype "passive"))
      (node (ref "U2") (pin "28") (pinfunction "GND_28") (pintype "passive"))
      (node (ref "U2") (pin "31") (pinfunction "GND_31") (pintype "passive"))
      (node (ref "U2") (pin "33") (pinfunction "GND_33") (pintype "passive"))
      (node (ref "U2") (pin "4") (pinfunction "GND_4") (pintype "passive"))
      (node (ref "U2") (pin "7") (pinfunction "GND_7") (pintype "passive"))
      (node (ref "U20") (pin "1") (pinfunction "A0_1") (pintype "input"))
      (node (ref "U20") (pin "2") (pinfunction "A1_2") (pintype "input"))
      (node (ref "U20") (pin "3") (pinfunction "NC_3") (pintype "passive"))
      (node (ref "U20") (pin "4") (pinfunction "GND_4") (pintype "power_in"))
      (node (ref "U20") (pin "7") (pinfunction "WP_7") (pintype "input"))
      (node (ref "U21") (pin "2") (pinfunction "GND_2") (pintype "power_in"))
      (node (ref "U3") (pin "1") (pinfunction "GND_1") (pintype "passive"))
      (node (ref "U3") (pin "3") (pinfunction "GND_3") (pintype "passive"))
      (node (ref "U3") (pin "4") (pinfunction "GND_4") (pintype "power_in"))
      (node (ref "U3") (pin "6") (pinfunction "GND_6") (pintype "passive"))
      (node (ref "U4") (pin "2") (pinfunction "GND_2") (pintype "power_in"))
      (node (ref "U4") (pin "4") (pinfunction "GND_4") (pintype "passive"))
      (node (ref "U5") (pin "1") (pinfunction "GND_1") (pintype "passive"))
      (node (ref "U5") (pin "3") (pinfunction "GND_3") (pintype "passive"))
      (node (ref "U5") (pin "5") (pinfunction "GND_5") (pintype "passive"))
      (node (ref "U5") (pin "7") (pinfunction "GND_7") (pintype "passive"))
      (node (ref "U6") (pin "1") (pinfunction "GND_1") (pintype "passive"))
      (node (ref "U6") (pin "3") (pinfunction "GND_3") (pintype "passive"))
      (node (ref "U6") (pin "4") (pinfunction "GND_4") (pintype "power_in"))
      (node (ref "U6") (pin "6") (pinfunction "GND_6") (pintype "passive"))
      (node (ref "U7") (pin "2") (pinfunction "GND_2") (pintype "power_in"))
      (node (ref "U7") (pin "4") (pinfunction "GND_4") (pintype "passive"))
      (node (ref "U8") (pin "1") (pinfunction "GND_1") (pintype "passive"))
      (node (ref "U8") (pin "3") (pinfunction "GND_3") (pintype "passive"))
      (node (ref "U8") (pin "5") (pinfunction "GND_5") (pintype "passive"))
      (node (ref "U8") (pin "7") (pinfunction "GND_7") (pintype "passive"))
      (node (ref "U9") (pin "12") (pinfunction "Q_IN_12") (pintype "passive"))
      (node (ref "U9") (pin "13") (pinfunction "I_IN_13") (pintype "passive"))
      (node (ref "U9") (pin "26") (pinfunction "GND_26") (pintype "passive"))
      (node (ref "U9") (pin "28") (pinfunction "GND_28") (pintype "passive"))
      (node (ref "U9") (pin "31") (pinfunction "GND_31") (pintype "passive"))
      (node (ref "U9") (pin "33") (pinfunction "GND_33") (pintype "passive"))
      (node (ref "U9") (pin "4") (pinfunction "GND_4") (pintype "passive"))
      (node (ref "U9") (pin "7") (pinfunction "GND_7") (pintype "passive"))
      (node (ref "VD1") (pin "K") (pintype "passive"))
      (node (ref "VD2") (pin "K") (pintype "passive"))
      (node (ref "VD3") (pin "K") (pintype "passive"))
      (node (ref "VD4") (pin "K") (pintype "passive"))
      (node (ref "VD5") (pin "K") (pintype "passive"))
    )
    (net (code "36") (name "Net-(J1-Signal)") (class "Default")
      (node (ref "C18") (pin "2") (pintype "passive"))
      (node (ref "D1") (pin "3") (pintype "passive"))
      (node (ref "J1") (pin "1") (pinfunction "Signal_1") (pintype "input"))
    )
    (net (code "37") (name "Net-(J2-Signal)") (class "Default")
      (node (ref "C28") (pin "2") (pintype "passive"))
      (node (ref "D2") (pin "3") (pintype "passive"))
      (node (ref "J2") (pin "1") (pinfunction "Signal_1") (pintype "input"))
    )
    (net (code "38") (name "Net-(J3-Signal)") (class "Default")
      (node (ref "C46") (pin "2") (pintype "passive"))
      (node (ref "D3") (pin "3") (pintype "passive"))
      (node (ref "J3") (pin "1") (pinfunction "Signal_1") (pintype "input"))
    )
    (net (code "39") (name "Net-(J4-Signal)") (class "Default")
      (node (ref "C56") (pin "2") (pintype "passive"))
      (node (ref "D4") (pin "3") (pintype "passive"))
      (node (ref "J4") (pin "1") (pinfunction "Signal_1") (pintype "input"))
    )
    (net (code "40") (name "Net-(J5-ID)") (class "Default")
      (node (ref "J5") (pin "4") (pinfunction "ID_4") (pintype "passive"))
      (node (ref "R2") (pin "2") (pintype "passive"))
    )
    (net (code "41") (name "Net-(R1-Pad2)") (class "Default")
      (node (ref "R1") (pin "2") (pintype "passive"))
      (node (ref "VD1") (pin "A") (pintype "passive"))
    )
    (net (code "42") (name "Net-(R4-Pad2)") (class "Default")
      (node (ref "R4") (pin "2") (pintype "passive"))
      (node (ref "VD2") (pin "A") (pintype "passive"))
    )
    (net (code "43") (name "Net-(R5-Pad2)") (class "Default")
      (node (ref "R5") (pin "2") (pintype "passive"))
      (node (ref "VD3") (pin "A") (pintype "passive"))
    )
    (net (code "44") (name "Net-(R6-Pad2)") (class "Default")
      (node (ref "R6") (pin "2") (pintype "passive"))
      (node (ref "VD4") (pin "A") (pintype "passive"))
    )
    (net (code "45") (name "Net-(R9-Pad2)") (class "Default")
      (node (ref "R9") (pin "2") (pintype "passive"))
      (node (ref "VD5") (pin "A") (pintype "passive"))
    )
    (net (code "46") (name "Net-(U1-VR_ANA1)") (class "Default")
      (node (ref "C8") (pin "1") (pintype "passive"))
      (node (ref "U1") (pin "3") (pinfunction "VR_ANA1_3") (pintype "passive"))
    )
    (net (code "47") (name "Net-(U1-VR_ANA2)") (class "Default")
      (node (ref "C3") (pin "1") (pintype "passive"))
      (node (ref "U1") (pin "25") (pinfunction "VR_ANA2_25") (pintype "passive"))
    )
    (net (code "48") (name "Net-(U1-VR_DIG)") (class "Default")
      (node (ref "C7") (pin "1") (pintype "passive"))
      (node (ref "U1") (pin "5") (pinfunction "VR_DIG_5") (pintype "passive"))
    )
    (net (code "49") (name "Net-(U1-VR_PA)") (class "Default")
      (node (ref "C10") (pin "1") (pintype "passive"))
      (node (ref "U1") (pin "1") (pinfunction "VR_PA_1") (pintype "passive"))
    )
    (net (code "50") (name "Net-(U1-XTB)") (class "Default")
      (node (ref "C19") (pin "2") (pintype "passive"))
      (node (ref "U1") (pin "8") (pinfunction "XTB_8") (pintype "passive"))
    )
    (net (code "51") (name "Net-(U2-VR_ANA1)") (class "Default")
      (node (ref "C12") (pin "1") (pintype "passive"))
      (node (ref "U2") (pin "3") (pinfunction "VR_ANA1_3") (pintype "passive"))
    )
    (net (code "52") (name "Net-(U2-VR_ANA2)") (class "Default")
      (node (ref "C5") (pin "1") (pintype "passive"))
      (node (ref "U2") (pin "25") (pinfunction "VR_ANA2_25") (pintype "passive"))
    )
    (net (code "53") (name "Net-(U2-VR_DIG)") (class "Default")
      (node (ref "C11") (pin "1") (pintype "passive"))
      (node (ref "U2") (pin "5") (pinfunction "VR_DIG_5") (pintype "passive"))
    )
    (net (code "54") (name "Net-(U2-VR_PA)") (class "Default")
      (node (ref "C14") (pin "1") (pintype "passive"))
      (node (ref "U2") (pin "1") (pinfunction "VR_PA_1") (pintype "passive"))
    )
    (net (code "55") (name "Net-(U2-XTB)") (class "Default")
      (node (ref "C20") (pin "2") (pintype "passive"))
      (node (ref "U2") (pin "8") (pinfunction "XTB_8") (pintype "passive"))
    )
    (net (code "56") (name "Net-(U3-IN)") (class "Default")
      (node (ref "C16") (pin "1") (pintype "passive"))
      (node (ref "U3") (pin "2") (pinfunction "IN_2") (pintype "passive"))
    )
    (net (code "57") (name "Net-(U3-OUT)") (class "Default")
      (node (ref "C15") (pin "2") (pintype "passive"))
      (node (ref "U3") (pin "5") (pinfunction "OUT_5") (pintype "passive"))
    )
    (net (code "58") (name "Net-(U4-IN)") (class "Default")
      (node (ref "C17") (pin "1") (pintype "passive"))
      (node (ref "U4") (pin "3") (pinfunction "IN_3") (pintype "passive"))
    )
    (net (code "59") (name "Net-(U4-OUT)") (class "Default")
      (node (ref "C16") (pin "2") (pintype "passive"))
      (node (ref "L1") (pin "1") (pintype "passive"))
      (node (ref "U4") (pin "1") (pinfunction "OUT_1") (pintype "passive"))
    )
    (net (code "60") (name "Net-(U5-IN)") (class "Default")
      (node (ref "C18") (pin "1") (pintype "passive"))
      (node (ref "U5") (pin "8") (pinfunction "IN_8") (pintype "passive"))
    )
    (net (code "61") (name "Net-(U5-OUT)") (class "Default")
      (node (ref "C17") (pin "2") (pintype "passive"))
      (node (ref "U5") (pin "4") (pinfunction "OUT_4") (pintype "power_in"))
    )
    (net (code "62") (name "Net-(U6-IN)") (class "Default")
      (node (ref "C26") (pin "1") (pintype "passive"))
      (node (ref "U6") (pin "2") (pinfunction "IN_2") (pintype "passive"))
    )
    (net (code "63") (name "Net-(U6-OUT)") (class "Default")
      (node (ref "C25") (pin "2") (pintype "passive"))
      (node (ref "U6") (pin "5") (pinfunction "OUT_5") (pintype "passive"))
    )
    (net (code "64") (name "Net-(U7-IN)") (class "Default")
      (node (ref "C27") (pin "1") (pintype "passive"))
      (node (ref "U7") (pin "3") (pinfunction "IN_3") (pintype "passive"))
    )
    (net (code "65") (name "Net-(U7-OUT)") (class "Default")
      (node (ref "C26") (pin "2") (pintype "passive"))
      (node (ref "L2") (pin "1") (pintype "passive"))
      (node (ref "U7") (pin "1") (pinfunction "OUT_1") (pintype "passive"))
    )
    (net (code "66") (name "Net-(U8-IN)") (class "Default")
      (node (ref "C28") (pin "1") (pintype "passive"))
      (node (ref "U8") (pin "8") (pinfunction "IN_8") (pintype "passive"))
    )
    (net (code "67") (name "Net-(U8-OUT)") (class "Default")
      (node (ref "C27") (pin "2") (pintype "passive"))
      (node (ref "U8") (pin "4") (pinfunction "OUT_4") (pintype "power_in"))
    )
    (net (code "68") (name "Net-(U9-VR_ANA1)") (class "Default")
      (node (ref "C36") (pin "1") (pintype "passive"))
      (node (ref "U9") (pin "3") (pinfunction "VR_ANA1_3") (pintype "passive"))
    )
    (net (code "69") (name "Net-(U9-VR_ANA2)") (class "Default")
      (node (ref "C29") (pin "1") (pintype "passive"))
      (node (ref "U9") (pin "25") (pinfunction "VR_ANA2_25") (pintype "passive"))
    )
    (net (code "70") (name "Net-(U9-VR_DIG)") (class "Default")
      (node (ref "C35") (pin "1") (pintype "passive"))
      (node (ref "U9") (pin "5") (pinfunction "VR_DIG_5") (pintype "passive"))
    )
    (net (code "71") (name "Net-(U9-VR_PA)") (class "Default")
      (node (ref "C38") (pin "1") (pintype "passive"))
      (node (ref "U9") (pin "1") (pinfunction "VR_PA_1") (pintype "passive"))
    )
    (net (code "72") (name "Net-(U9-XTB)") (class "Default")
      (node (ref "C47") (pin "2") (pintype "passive"))
      (node (ref "U9") (pin "8") (pinfunction "XTB_8") (pintype "passive"))
    )
    (net (code "73") (name "Net-(U10-VR_ANA1)") (class "Default")
      (node (ref "C40") (pin "1") (pintype "passive"))
      (node (ref "U10") (pin "3") (pinfunction "VR_ANA1_3") (pintype "passive"))
    )
    (net (code "74") (name "Net-(U10-VR_ANA2)") (class "Default")
      (node (ref "C30") (pin "1") (pintype "passive"))
      (node (ref "U10") (pin "25") (pinfunction "VR_ANA2_25") (pintype "passive"))
    )
    (net (code "75") (name "Net-(U10-VR_DIG)") (class "Default")
      (node (ref "C39") (pin "1") (pintype "passive"))
      (node (ref "U10") (pin "5") (pinfunction "VR_DIG_5") (pintype "passive"))
    )
    (net (code "76") (name "Net-(U10-VR_PA)") (class "Default")
      (node (ref "C42") (pin "1") (pintype "passive"))
      (node (ref "U10") (pin "1") (pinfunction "VR_PA_1") (pintype "passive"))
    )
    (net (code "77") (name "Net-(U10-XTB)") (class "Default")
      (node (ref "C48") (pin "2") (pintype "passive"))
      (node (ref "U10") (pin "8") (pinfunction "XTB_8") (pintype "passive"))
    )
    (net (code "78") (name "Net-(U11-IN)") (class "Default")
      (node (ref "C44") (pin "1") (pintype "passive"))
      (node (ref "U11") (pin "2") (pinfunction "IN_2") (pintype "passive"))
    )
    (net (code "79") (name "Net-(U11-OUT)") (class "Default")
      (node (ref "C43") (pin "2") (pintype "passive"))
      (node (ref "U11") (pin "5") (pinfunction "OUT_5") (pintype "passive"))
    )
    (net (code "80") (name "Net-(U12-IN)") (class "Default")
      (node (ref "C45") (pin "1") (pintype "passive"))
      (node (ref "U12") (pin "3") (pinfunction "IN_3") (pintype "passive"))
    )
    (net (code "81") (name "Net-(U12-OUT)") (class "Default")
      (node (ref "C44") (pin "2") (pintype "passive"))
      (node (ref "L3") (pin "1") (pintype "passive"))
      (node (ref "U12") (pin "1") (pinfunction "OUT_1") (pintype "passive"))
    )
    (net (code "82") (name "Net-(U13-IN)") (class "Default")
      (node (ref "C46") (pin "1") (pintype "passive"))
      (node (ref "U13") (pin "8") (pinfunction "IN_8") (pintype "passive"))
    )
    (net (code "83") (name "Net-(U13-OUT)") (class "Default")
      (node (ref "C45") (pin "2") (pintype "passive"))
      (node (ref "U13") (pin "4") (pinfunction "OUT_4") (pintype "power_in"))
    )
    (net (code "84") (name "Net-(U14-IN)") (class "Default")
      (node (ref "C54") (pin "1") (pintype "passive"))
      (node (ref "U14") (pin "2") (pinfunction "IN_2") (pintype "passive"))
    )
    (net (code "85") (name "Net-(U14-OUT)") (class "Default")
      (node (ref "C53") (pin "2") (pintype "passive"))
      (node (ref "U14") (pin "5") (pinfunction "OUT_5") (pintype "passive"))
    )
    (net (code "86") (name "Net-(U15-IN)") (class "Default")
      (node (ref "C55") (pin "1") (pintype "passive"))
      (node (ref "U15") (pin "3") (pinfunction "IN_3") (pintype "passive"))
    )
    (net (code "87") (name "Net-(U15-OUT)") (class "Default")
      (node (ref "C54") (pin "2") (pintype "passive"))
      (node (ref "L4") (pin "1") (pintype "passive"))
      (node (ref "U15") (pin "1") (pinfunction "OUT_1") (pintype "passive"))
    )
    (net (code "88") (name "Net-(U16-IN)") (class "Default")
      (node (ref "C56") (pin "1") (pintype "passive"))
      (node (ref "U16") (pin "8") (pinfunction "IN_8") (pintype "passive"))
    )
    (net (code "89") (name "Net-(U16-OUT)") (class "Default")
      (node (ref "C55") (pin "2") (pintype "passive"))
      (node (ref "U16") (pin "4") (pinfunction "OUT_4") (pintype "power_in"))
    )
    (net (code "90") (name "Net-(U18A-PD1{slash}FD9)") (class "Default")
      (node (ref "R4") (pin "1") (pintype "passive"))
      (node (ref "U18") (pin "46") (pinfunction "PD1/FD9_46") (pintype "bidirectional"))
    )
    (net (code "91") (name "Net-(U18A-PD3{slash}FD11)") (class "Default")
      (node (ref "R5") (pin "1") (pintype "passive"))
      (node (ref "U18") (pin "48") (pinfunction "PD3/FD11_48") (pintype "bidirectional"))
    )
    (net (code "92") (name "Net-(U18A-PD5{slash}FD13)") (class "Default")
      (node (ref "R6") (pin "1") (pintype "passive"))
      (node (ref "U18") (pin "50") (pinfunction "PD5/FD13_50") (pintype "bidirectional"))
    )
    (net (code "93") (name "Net-(U18A-PD7{slash}FD15)") (class "Default")
      (node (ref "R9") (pin "1") (pintype "passive"))
      (node (ref "U18") (pin "52") (pinfunction "PD7/FD15_52") (pintype "bidirectional"))
    )
    (net (code "94") (name "Net-(U18B-RESET#)") (class "Default")
      (node (ref "R12") (pin "1") (pintype "passive"))
      (node (ref "U18") (pin "42") (pinfunction "RESET#_42") (pintype "input"))
    )
    (net (code "95") (name "Net-(U18B-WAKEUP)") (class "Default")
      (node (ref "R11") (pin "2") (pintype "passive"))
      (node (ref "U18") (pin "44") (pinfunction "WAKEUP_44") (pintype "input"))
    )
    (net (code "96") (name "Net-(U19-EN)") (class "Default")
      (node (ref "R3") (pin "2") (pintype "passive"))
      (node (ref "U19") (pin "3") (pinfunction "EN_3") (pintype "input"))
    )
    (net (code "97") (name "Net-(U19-NR)") (class "Default")
      (node (ref "C67") (pin "2") (pintype "passive"))
      (node (ref "U19") (pin "4") (pinfunction "NR_4") (pintype "passive"))
    )
    (net (code "98") (name "Net-(U20-SDA)") (class "Default")
      (node (ref "P1") (pin "2") (pinfunction "2_2") (pintype "passive"))
      (node (ref "U20") (pin "5") (pinfunction "SDA_5") (pintype "bidirectional"))
    )
    (net (code "99") (name "Net-(U21-EN)") (class "Default")
      (node (ref "R10") (pin "2") (pintype "passive"))
      (node (ref "U21") (pin "3") (pinfunction "EN_3") (pintype "input"))
    )
    (net (code "100") (name "Net-(U21-NR)") (class "Default")
      (node (ref "C73") (pin "2") (pintype "passive"))
      (node (ref "U21") (pin "4") (pinfunction "NR_4") (pintype "passive"))
    )
    (net (code "101") (name "unconnected-(U1-CLK_IN-Pad11)") (class "Default")
      (node (ref "U1") (pin "11") (pinfunction "CLK_IN_11") (pintype "passive"))
    )
    (net (code "102") (name "unconnected-(U1-DIO0-Pad21)") (class "Default")
      (node (ref "U1") (pin "21") (pinfunction "DIO0_21") (pintype "passive"))
    )
    (net (code "103") (name "unconnected-(U1-DIO1-Pad22)") (class "Default")
      (node (ref "U1") (pin "22") (pinfunction "DIO1_22") (pintype "passive"))
    )
    (net (code "104") (name "unconnected-(U1-DIO2-Pad23)") (class "Default")
      (node (ref "U1") (pin "23") (pinfunction "DIO2_23") (pintype "passive"))
    )
    (net (code "105") (name "unconnected-(U1-DIO3-Pad24)") (class "Default")
      (node (ref "U1") (pin "24") (pinfunction "DIO3_24") (pintype "passive"))
    )
    (net (code "106") (name "unconnected-(U1-RF_ON-Pad29)") (class "Default")
      (node (ref "U1") (pin "29") (pinfunction "RF_ON_29") (pintype "passive"))
    )
    (net (code "107") (name "unconnected-(U1-RF_OP-Pad30)") (class "Default")
      (node (ref "U1") (pin "30") (pinfunction "RF_OP_30") (pintype "passive"))
    )
    (net (code "108") (name "unconnected-(U1-XTA-Pad6)") (class "Default")
      (node (ref "U1") (pin "6") (pinfunction "XTA_6") (pintype "passive"))
    )
    (net (code "109") (name "unconnected-(U2-CLK_IN-Pad11)") (class "Default")
      (node (ref "U2") (pin "11") (pinfunction "CLK_IN_11") (pintype "passive"))
    )
    (net (code "110") (name "unconnected-(U2-CLK_OUT-Pad10)") (class "Default")
      (node (ref "U2") (pin "10") (pinfunction "CLK_OUT_10") (pintype "passive"))
    )
    (net (code "111") (name "unconnected-(U2-DIO0-Pad21)") (class "Default")
      (node (ref "U2") (pin "21") (pinfunction "DIO0_21") (pintype "passive"))
    )
    (net (code "112") (name "unconnected-(U2-DIO1-Pad22)") (class "Default")
      (node (ref "U2") (pin "22") (pinfunction "DIO1_22") (pintype "passive"))
    )
    (net (code "113") (name "unconnected-(U2-DIO2-Pad23)") (class "Default")
      (node (ref "U2") (pin "23") (pinfunction "DIO2_23") (pintype "passive"))
    )
    (net (code "114") (name "unconnected-(U2-DIO3-Pad24)") (class "Default")
      (node (ref "U2") (pin "24") (pinfunction "DIO3_24") (pintype "passive"))
    )
    (net (code "115") (name "unconnected-(U2-RF_ON-Pad29)") (class "Default")
      (node (ref "U2") (pin "29") (pinfunction "RF_ON_29") (pintype "passive"))
    )
    (net (code "116") (name "unconnected-(U2-RF_OP-Pad30)") (class "Default")
      (node (ref "U2") (pin "30") (pinfunction "RF_OP_30") (pintype "passive"))
    )
    (net (code "117") (name "unconnected-(U2-XTA-Pad6)") (class "Default")
      (node (ref "U2") (pin "6") (pinfunction "XTA_6") (pintype "passive"))
    )
    (net (code "118") (name "unconnected-(U5-NC-Pad2)") (class "Default")
      (node (ref "U5") (pin "2") (pinfunction "NC_2") (pintype "passive"))
    )
    (net (code "119") (name "unconnected-(U5-NC-Pad6)") (class "Default")
      (node (ref "U5") (pin "6") (pinfunction "NC_6") (pintype "passive"))
    )
    (net (code "120") (name "unconnected-(U8-NC-Pad2)") (class "Default")
      (node (ref "U8") (pin "2") (pinfunction "NC_2") (pintype "passive"))
    )
    (net (code "121") (name "unconnected-(U8-NC-Pad6)") (class "Default")
      (node (ref "U8") (pin "6") (pinfunction "NC_6") (pintype "passive"))
    )
    (net (code "122") (name "unconnected-(U9-CLK_IN-Pad11)") (class "Default")
      (node (ref "U9") (pin "11") (pinfunction "CLK_IN_11") (pintype "passive"))
    )
    (net (code "123") (name "unconnected-(U9-CLK_OUT-Pad10)") (class "Default")
      (node (ref "U9") (pin "10") (pinfunction "CLK_OUT_10") (pintype "passive"))
    )
    (net (code "124") (name "unconnected-(U9-DIO0-Pad21)") (class "Default")
      (node (ref "U9") (pin "21") (pinfunction "DIO0_21") (pintype "passive"))
    )
    (net (code "125") (name "unconnected-(U9-DIO1-Pad22)") (class "Default")
      (node (ref "U9") (pin "22") (pinfunction "DIO1_22") (pintype "passive"))
    )
    (net (code "126") (name "unconnected-(U9-DIO2-Pad23)") (class "Default")
      (node (ref "U9") (pin "23") (pinfunction "DIO2_23") (pintype "passive"))
    )
    (net (code "127") (name "unconnected-(U9-DIO3-Pad24)") (class "Default")
      (node (ref "U9") (pin "24") (pinfunction "DIO3_24") (pintype "passive"))
    )
    (net (code "128") (name "unconnected-(U9-RF_ON-Pad29)") (class "Default")
      (node (ref "U9") (pin "29") (pinfunction "RF_ON_29") (pintype "passive"))
    )
    (net (code "129") (name "unconnected-(U9-RF_OP-Pad30)") (class "Default")
      (node (ref "U9") (pin "30") (pinfunction "RF_OP_30") (pintype "passive"))
    )
    (net (code "130") (name "unconnected-(U9-XTA-Pad6)") (class "Default")
      (node (ref "U9") (pin "6") (pinfunction "XTA_6") (pintype "passive"))
    )
    (net (code "131") (name "unconnected-(U10-CLK_IN-Pad11)") (class "Default")
      (node (ref "U10") (pin "11") (pinfunction "CLK_IN_11") (pintype "passive"))
    )
    (net (code "132") (name "unconnected-(U10-CLK_OUT-Pad10)") (class "Default")
      (node (ref "U10") (pin "10") (pinfunction "CLK_OUT_10") (pintype "passive"))
    )
    (net (code "133") (name "unconnected-(U10-DIO0-Pad21)") (class "Default")
      (node (ref "U10") (pin "21") (pinfunction "DIO0_21") (pintype "passive"))
    )
    (net (code "134") (name "unconnected-(U10-DIO1-Pad22)") (class "Default")
      (node (ref "U10") (pin "22") (pinfunction "DIO1_22") (pintype "passive"))
    )
    (net (code "135") (name "unconnected-(U10-DIO2-Pad23)") (class "Default")
      (node (ref "U10") (pin "23") (pinfunction "DIO2_23") (pintype "passive"))
    )
    (net (code "136") (name "unconnected-(U10-DIO3-Pad24)") (class "Default")
      (node (ref "U10") (pin "24") (pinfunction "DIO3_24") (pintype "passive"))
    )
    (net (code "137") (name "unconnected-(U10-RF_ON-Pad29)") (class "Default")
      (node (ref "U10") (pin "29") (pinfunction "RF_ON_29") (pintype "passive"))
    )
    (net (code "138") (name "unconnected-(U10-RF_OP-Pad30)") (class "Default")
      (node (ref "U10") (pin "30") (pinfunction "RF_OP_30") (pintype "passive"))
    )
    (net (code "139") (name "unconnected-(U10-XTA-Pad6)") (class "Default")
      (node (ref "U10") (pin "6") (pinfunction "XTA_6") (pintype "passive"))
    )
    (net (code "140") (name "unconnected-(U13-NC-Pad2)") (class "Default")
      (node (ref "U13") (pin "2") (pinfunction "NC_2") (pintype "passive"))
    )
    (net (code "141") (name "unconnected-(U13-NC-Pad6)") (class "Default")
      (node (ref "U13") (pin "6") (pinfunction "NC_6") (pintype "passive"))
    )
    (net (code "142") (name "unconnected-(U16-NC-Pad2)") (class "Default")
      (node (ref "U16") (pin "2") (pinfunction "NC_2") (pintype "passive"))
    )
    (net (code "143") (name "unconnected-(U16-NC-Pad6)") (class "Default")
      (node (ref "U16") (pin "6") (pinfunction "NC_6") (pintype "passive"))
    )
    (net (code "144") (name "unconnected-(U18A-PD0{slash}FD8-Pad45)") (class "Default")
      (node (ref "U18") (pin "45") (pinfunction "PD0/FD8_45") (pintype "bidirectional"))
    )
    (net (code "145") (name "unconnected-(U18A-PD2{slash}FD10-Pad47)") (class "Default")
      (node (ref "U18") (pin "47") (pinfunction "PD2/FD10_47") (pintype "bidirectional"))
    )
    (net (code "146") (name "unconnected-(U18A-PD4{slash}FD12-Pad49)") (class "Default")
      (node (ref "U18") (pin "49") (pinfunction "PD4/FD12_49") (pintype "bidirectional"))
    )
    (net (code "147") (name "unconnected-(U18A-PD6{slash}FD14-Pad51)") (class "Default")
      (node (ref "U18") (pin "51") (pinfunction "PD6/FD14_51") (pintype "bidirectional"))
    )
    (net (code "148") (name "unconnected-(U18B-CLKOUT-Pad54)") (class "Default")
      (node (ref "U18") (pin "54") (pinfunction "CLKOUT_54") (pintype "tri_state"))
    )
    (net (code "149") (name "unconnected-(U18B-CTL0{slash}FLAGA-Pad29)") (class "Default")
      (node (ref "U18") (pin "29") (pinfunction "CTL0/FLAGA_29") (pintype "tri_state"))
    )
    (net (code "150") (name "unconnected-(U18B-CTL1{slash}FLAGB-Pad30)") (class "Default")
      (node (ref "U18") (pin "30") (pinfunction "CTL1/FLAGB_30") (pintype "tri_state"))
    )
    (net (code "151") (name "unconnected-(U18B-CTL2{slash}FLAGC-Pad31)") (class "Default")
      (node (ref "U18") (pin "31") (pinfunction "CTL2/FLAGC_31") (pintype "tri_state"))
    )
    (net (code "152") (name "unconnected-(U18B-RDY0{slash}SLRD-Pad1)") (class "Default")
      (node (ref "U18") (pin "1") (pinfunction "RDY0/SLRD_1") (pintype "input"))
    )
    (net (code "153") (name "unconnected-(U18B-RDY1{slash}SLWR-Pad2)") (class "Default")
      (node (ref "U18") (pin "2") (pinfunction "RDY1/SLWR_2") (pintype "input"))
    )
  )
)
